# Load_cell_1_0.net
KiCad netlist of a schematic drawn in EAGLE
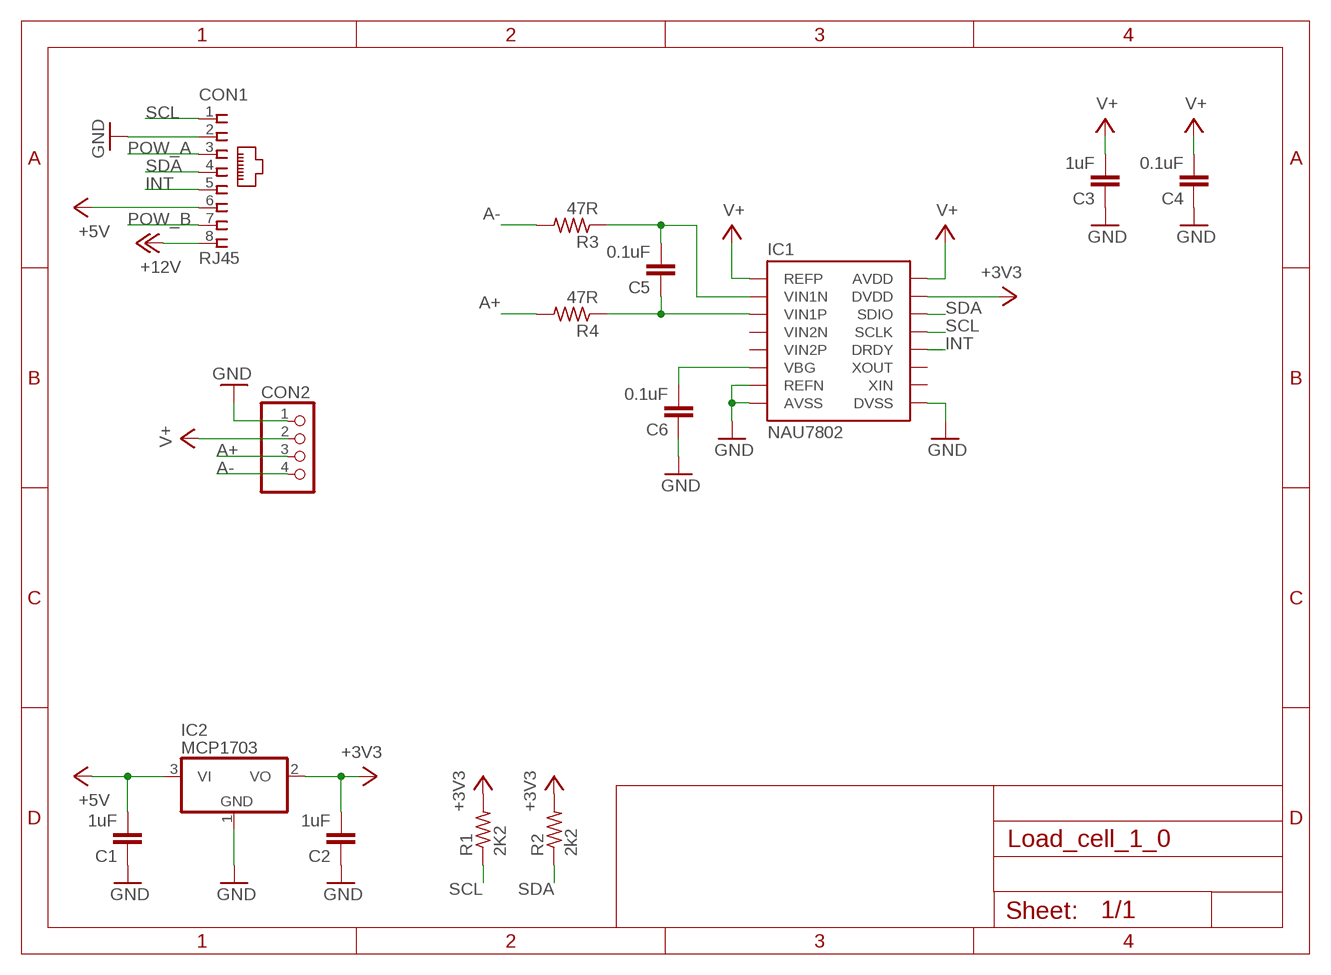
[diagram p0: schematic, sheet 1]

(export (version "E")
  (design (tool "Eeschema 10.0.6"))
  (components
    (comp (ref "C1")
      (value "1uF")
      (footprint "eagle-import:C0603K")
      (libsource (lib "eagle-import") (part "C-EUC0603K"))
    )
    (comp (ref "C2")
      (value "1uF")
      (footprint "eagle-import:C0603K")
      (libsource (lib "eagle-import") (part "C-EUC0603K"))
    )
    (comp (ref "C3")
      (value "1uF")
      (footprint "eagle-import:C0603K")
      (libsource (lib "eagle-import") (part "C-EUC0603K"))
    )
    (comp (ref "C4")
      (value "0.1uF")
      (footprint "eagle-import:C0603K")
      (libsource (lib "eagle-import") (part "C-EUC0603K"))
    )
    (comp (ref "C5")
      (value "0.1uF")
      (footprint "eagle-import:C0603K")
      (libsource (lib "eagle-import") (part "C-EUC0603K"))
    )
    (comp (ref "C6")
      (value "0.1uF")
      (footprint "eagle-import:C0603K")
      (libsource (lib "eagle-import") (part "C-EUC0603K"))
    )
    (comp (ref "CON1")
      (value "RJ45")
      (footprint "eagle-import:RJ45-NO-SHIELD-VERTICAL")
      (libsource (lib "eagle-import") (part "RJ45VERTICAL"))
    )
    (comp (ref "CON2")
      (value "PINHD-1X4")
      (footprint "eagle-import:1X04")
      (libsource (lib "eagle-import") (part "PINHD-1X4"))
    )
    (comp (ref "IC1")
      (value "NAU7802")
      (footprint "eagle-import:SO16")
      (libsource (lib "eagle-import") (part "NAU7802SOIC"))
    )
    (comp (ref "IC2")
      (value "MCP1703")
      (footprint "eagle-import:SOT23")
      (libsource (lib "eagle-import") (part "MCP1703CB"))
    )
    (comp (ref "R1")
      (value "2K2")
      (footprint "eagle-import:R0603")
      (libsource (lib "eagle-import") (part "R-US_R0603"))
    )
    (comp (ref "R2")
      (value "2k2")
      (footprint "eagle-import:R0603")
      (libsource (lib "eagle-import") (part "R-US_R0603"))
    )
    (comp (ref "R3")
      (value "47R")
      (footprint "eagle-import:R0603")
      (libsource (lib "eagle-import") (part "R-US_R0603"))
    )
    (comp (ref "R4")
      (value "47R")
      (footprint "eagle-import:R0603")
      (libsource (lib "eagle-import") (part "R-US_R0603"))
    )
  )
  (nets
    (net (code "1") (name "+3V3") (class "Default")
      (node (ref "C2") (pin "2") (pinfunction "2_2") (pintype "passive"))
      (node (ref "IC1") (pin "15") (pinfunction "DVDD_15") (pintype "bidirectional"))
      (node (ref "IC2") (pin "2") (pinfunction "VO_2") (pintype "passive"))
      (node (ref "R1") (pin "2") (pinfunction "2_2") (pintype "passive"))
      (node (ref "R2") (pin "2") (pinfunction "2_2") (pintype "passive"))
    )
    (net (code "2") (name "+5V") (class "Default")
      (node (ref "C1") (pin "2") (pinfunction "2_2") (pintype "passive"))
      (node (ref "CON1") (pin "6") (pinfunction "6_6") (pintype "passive"))
      (node (ref "IC2") (pin "3") (pinfunction "VI_3") (pintype "input"))
    )
    (net (code "3") (name "+12V") (class "Default")
      (node (ref "CON1") (pin "8") (pinfunction "8_8") (pintype "passive"))
    )
    (net (code "4") (name "/A+") (class "Default")
      (node (ref "CON2") (pin "3") (pinfunction "3_3") (pintype "passive"))
      (node (ref "R4") (pin "2") (pinfunction "2_2") (pintype "passive"))
    )
    (net (code "5") (name "/A-") (class "Default")
      (node (ref "CON2") (pin "4") (pinfunction "4_4") (pintype "passive"))
      (node (ref "R3") (pin "2") (pinfunction "2_2") (pintype "passive"))
    )
    (net (code "6") (name "/INT") (class "Default")
      (node (ref "CON1") (pin "5") (pinfunction "5_5") (pintype "passive"))
      (node (ref "IC1") (pin "12") (pinfunction "DRDY_12") (pintype "bidirectional"))
    )
    (net (code "7") (name "/POW_A") (class "Default")
      (node (ref "CON1") (pin "3") (pinfunction "3_3") (pintype "passive"))
    )
    (net (code "8") (name "/POW_B") (class "Default")
      (node (ref "CON1") (pin "7") (pinfunction "7_7") (pintype "passive"))
    )
    (net (code "9") (name "/SCL") (class "Default")
      (node (ref "CON1") (pin "1") (pinfunction "1_1") (pintype "passive"))
      (node (ref "IC1") (pin "13") (pinfunction "SCLK_13") (pintype "bidirectional"))
      (node (ref "R1") (pin "1") (pinfunction "1_1") (pintype "passive"))
    )
    (net (code "10") (name "/SDA") (class "Default")
      (node (ref "CON1") (pin "4") (pinfunction "4_4") (pintype "passive"))
      (node (ref "IC1") (pin "14") (pinfunction "SDIO_14") (pintype "bidirectional"))
      (node (ref "R2") (pin "1") (pinfunction "1_1") (pintype "passive"))
    )
    (net (code "11") (name "GND") (class "Default")
      (node (ref "C1") (pin "1") (pinfunction "1_1") (pintype "passive"))
      (node (ref "C2") (pin "1") (pinfunction "1_1") (pintype "passive"))
      (node (ref "C3") (pin "1") (pinfunction "1_1") (pintype "passive"))
      (node (ref "C4") (pin "1") (pinfunction "1_1") (pintype "passive"))
      (node (ref "C6") (pin "1") (pinfunction "1_1") (pintype "passive"))
      (node (ref "CON1") (pin "2") (pinfunction "2_2") (pintype "passive"))
      (node (ref "CON2") (pin "1") (pinfunction "1_1") (pintype "passive"))
      (node (ref "IC1") (pin "7") (pinfunction "REFN_7") (pintype "bidirectional"))
      (node (ref "IC1") (pin "8") (pinfunction "AVSS_8") (pintype "bidirectional"))
      (node (ref "IC1") (pin "9") (pinfunction "DVSS_9") (pintype "bidirectional"))
      (node (ref "IC2") (pin "1") (pinfunction "GND_1") (pintype "passive"))
    )
    (net (code "12") (name "Net-(IC1-VBG)") (class "Default")
      (node (ref "C6") (pin "2") (pinfunction "2_2") (pintype "passive"))
      (node (ref "IC1") (pin "6") (pinfunction "VBG_6") (pintype "bidirectional"))
    )
    (net (code "13") (name "Net-(IC1-VIN1N)") (class "Default")
      (node (ref "C5") (pin "2") (pinfunction "2_2") (pintype "passive"))
      (node (ref "IC1") (pin "2") (pinfunction "VIN1N_2") (pintype "bidirectional"))
      (node (ref "R3") (pin "1") (pinfunction "1_1") (pintype "passive"))
    )
    (net (code "14") (name "Net-(IC1-VIN1P)") (class "Default")
      (node (ref "C5") (pin "1") (pinfunction "1_1") (pintype "passive"))
      (node (ref "IC1") (pin "3") (pinfunction "VIN1P_3") (pintype "bidirectional"))
      (node (ref "R4") (pin "1") (pinfunction "1_1") (pintype "passive"))
    )
    (net (code "15") (name "V+") (class "Default")
      (node (ref "C3") (pin "2") (pinfunction "2_2") (pintype "passive"))
      (node (ref "C4") (pin "2") (pinfunction "2_2") (pintype "passive"))
      (node (ref "CON2") (pin "2") (pinfunction "2_2") (pintype "passive"))
      (node (ref "IC1") (pin "1") (pinfunction "REFP_1") (pintype "bidirectional"))
      (node (ref "IC1") (pin "16") (pinfunction "AVDD_16") (pintype "bidirectional"))
    )
    (net (code "16") (name "unconnected-(IC1-VIN2N-Pad4)") (class "Default")
      (node (ref "IC1") (pin "4") (pinfunction "VIN2N_4") (pintype "bidirectional"))
    )
    (net (code "17") (name "unconnected-(IC1-VIN2P-Pad5)") (class "Default")
      (node (ref "IC1") (pin "5") (pinfunction "VIN2P_5") (pintype "bidirectional"))
    )
    (net (code "18") (name "unconnected-(IC1-XIN-Pad10)") (class "Default")
      (node (ref "IC1") (pin "10") (pinfunction "XIN_10") (pintype "bidirectional"))
    )
    (net (code "19") (name "unconnected-(IC1-XOUT-Pad11)") (class "Default")
      (node (ref "IC1") (pin "11") (pinfunction "XOUT_11") (pintype "bidirectional"))
    )
  )
)
